# turntable.net
KiCad netlist of a schematic drawn in EAGLE
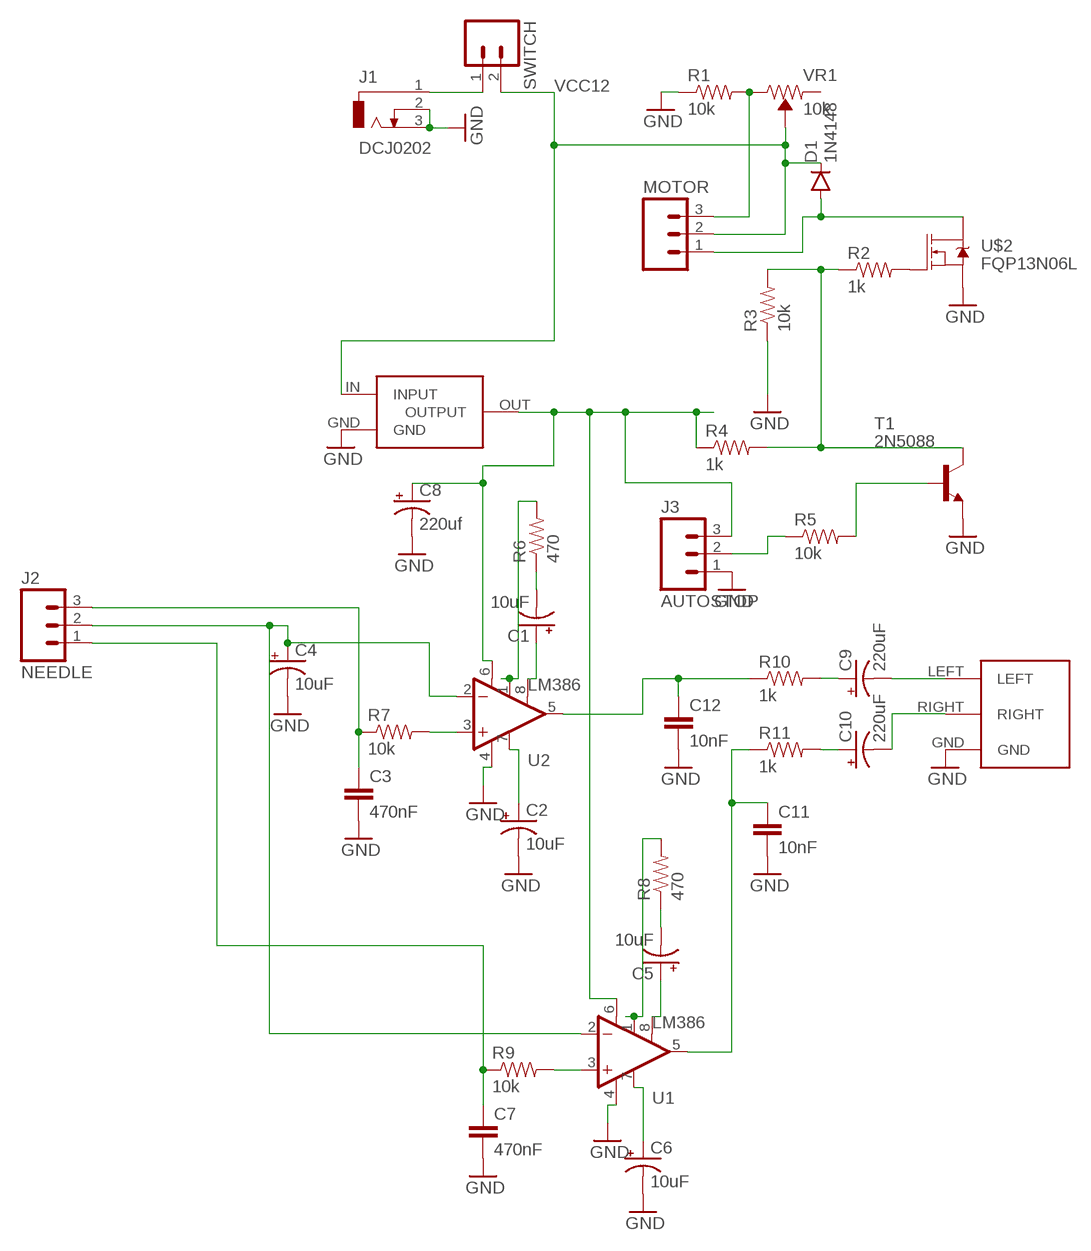
[diagram p0: schematic, sheet 1]

(export (version "E")
  (design (tool "Eeschema 10.0.6"))
  (components
    (comp (ref "C1")
      (value "10uF")
      (footprint "eagle-import:E5-5")
      (libsource (lib "eagle-import") (part "CPOL-USE5-5"))
    )
    (comp (ref "C2")
      (value "10uF")
      (footprint "eagle-import:E5-5")
      (libsource (lib "eagle-import") (part "CPOL-USE5-5"))
    )
    (comp (ref "C3")
      (value "470nF")
      (footprint "eagle-import:C15B8")
      (libsource (lib "eagle-import") (part "C15/8"))
    )
    (comp (ref "C4")
      (value "10uF")
      (footprint "eagle-import:E5-5")
      (libsource (lib "eagle-import") (part "CPOL-USE5-5"))
    )
    (comp (ref "C5")
      (value "10uF")
      (footprint "eagle-import:E5-5")
      (libsource (lib "eagle-import") (part "CPOL-USE5-5"))
    )
    (comp (ref "C6")
      (value "10uF")
      (footprint "eagle-import:E5-5")
      (libsource (lib "eagle-import") (part "CPOL-USE5-5"))
    )
    (comp (ref "C7")
      (value "470nF")
      (footprint "eagle-import:C15B8")
      (libsource (lib "eagle-import") (part "C15/8"))
    )
    (comp (ref "C8")
      (value "220uf")
      (footprint "eagle-import:TT5D10")
      (libsource (lib "eagle-import") (part "CPOL-USTT5D10"))
    )
    (comp (ref "C9")
      (value "220uF")
      (footprint "eagle-import:E5-5")
      (libsource (lib "eagle-import") (part "CPOL-USE5-5"))
    )
    (comp (ref "C10")
      (value "220uF")
      (footprint "eagle-import:E5-5")
      (libsource (lib "eagle-import") (part "CPOL-USE5-5"))
    )
    (comp (ref "C11")
      (value "10nF")
      (footprint "eagle-import:C5B2.5")
      (libsource (lib "eagle-import") (part "C5/2.5"))
    )
    (comp (ref "C12")
      (value "10nF")
      (footprint "eagle-import:C5B2.5")
      (libsource (lib "eagle-import") (part "C5/2.5"))
    )
    (comp (ref "D1")
      (value "1N4148")
      (footprint "eagle-import:DIODE-1N4148")
      (libsource (lib "eagle-import") (part "DIODE1N4148"))
    )
    (comp (ref "J1")
      (value "DCJ0202")
      (footprint "eagle-import:DCJ0202")
      (libsource (lib "eagle-import") (part "DCJ0202"))
    )
    (comp (ref "J2")
      (value "NEEDLE")
      (footprint "eagle-import:1X03")
      (libsource (lib "eagle-import") (part "M03PTH"))
    )
    (comp (ref "J3")
      (value "AUTOSTOP")
      (footprint "eagle-import:1X03")
      (libsource (lib "eagle-import") (part "M03PTH"))
    )
    (comp (ref "MOTOR")
      (value "M03PTH")
      (footprint "eagle-import:1X03")
      (libsource (lib "eagle-import") (part "M03PTH"))
    )
    (comp (ref "R1")
      (value "10k")
      (footprint "eagle-import:AXIAL-0.5")
      (libsource (lib "eagle-import") (part "RESISTORPTH-1/2W"))
    )
    (comp (ref "R2")
      (value "1k")
      (footprint "eagle-import:AXIAL-0.5")
      (libsource (lib "eagle-import") (part "RESISTORPTH-1/2W"))
    )
    (comp (ref "R3")
      (value "10k")
      (footprint "eagle-import:AXIAL-0.5")
      (libsource (lib "eagle-import") (part "RESISTORPTH-1/2W"))
    )
    (comp (ref "R4")
      (value "1k")
      (footprint "eagle-import:AXIAL-0.5")
      (libsource (lib "eagle-import") (part "RESISTORPTH-1/2W"))
    )
    (comp (ref "R5")
      (value "10k")
      (footprint "eagle-import:AXIAL-0.5")
      (libsource (lib "eagle-import") (part "RESISTORPTH-1/2W"))
    )
    (comp (ref "R6")
      (value "470")
      (footprint "eagle-import:AXIAL-0.5")
      (libsource (lib "eagle-import") (part "RESISTORPTH-1/2W"))
    )
    (comp (ref "R7")
      (value "10k")
      (footprint "eagle-import:AXIAL-0.5")
      (libsource (lib "eagle-import") (part "RESISTORPTH-1/2W"))
    )
    (comp (ref "R8")
      (value "470")
      (footprint "eagle-import:AXIAL-0.5")
      (libsource (lib "eagle-import") (part "RESISTORPTH-1/2W"))
    )
    (comp (ref "R9")
      (value "10k")
      (footprint "eagle-import:AXIAL-0.5")
      (libsource (lib "eagle-import") (part "RESISTORPTH-1/2W"))
    )
    (comp (ref "R10")
      (value "1k")
      (footprint "eagle-import:AXIAL-0.5")
      (libsource (lib "eagle-import") (part "RESISTORPTH-1/2W"))
    )
    (comp (ref "R11")
      (value "1k")
      (footprint "eagle-import:AXIAL-0.5")
      (libsource (lib "eagle-import") (part "RESISTORPTH-1/2W"))
    )
    (comp (ref "SWITCH")
      (value "M02PTH")
      (footprint "eagle-import:1X02")
      (libsource (lib "eagle-import") (part "M02PTH"))
    )
    (comp (ref "T1")
      (value "2N5088")
      (footprint "eagle-import:TO92")
      (libsource (lib "eagle-import") (part "2N5088"))
    )
    (comp (ref "U$1")
      (value "LD1117")
      (footprint "eagle-import:78XXL")
      (libsource (lib "eagle-import") (part "LD1117"))
    )
    (comp (ref "U$2")
      (value "FQP13N06L")
      (footprint "eagle-import:TO-220")
      (libsource (lib "eagle-import") (part "FQP13N06L"))
    )
    (comp (ref "U$3")
      (value "RCA")
      (footprint "eagle-import:RCA")
      (libsource (lib "eagle-import") (part "RCA"))
    )
    (comp (ref "U1")
      (value "LM386")
      (footprint "eagle-import:DIP08")
      (libsource (lib "eagle-import") (part "LM386"))
    )
    (comp (ref "U2")
      (value "LM386")
      (footprint "eagle-import:DIP08")
      (libsource (lib "eagle-import") (part "LM386"))
    )
    (comp (ref "VR1")
      (value "10k")
      (footprint "eagle-import:TRIMPOT-PTH-3386U")
      (libsource (lib "eagle-import") (part "TRIMPOT-PTH-10MM-KNOB-1/2W-10%"))
    )
  )
  (nets
    (net (code "1") (name "/VCC12") (class "Default")
      (node (ref "D1") (pin "C") (pinfunction "C_C") (pintype "passive"))
      (node (ref "MOTOR") (pin "2") (pinfunction "2_2") (pintype "passive"))
      (node (ref "SWITCH") (pin "2") (pinfunction "2_2") (pintype "passive"))
      (node (ref "U$1") (pin "IN") (pinfunction "INPUT_IN") (pintype "bidirectional"))
      (node (ref "VR1") (pin "2") (pinfunction "WIPER_2") (pintype "passive"))
    )
    (net (code "2") (name "GND") (class "Default")
      (node (ref "C11") (pin "2") (pinfunction "2_2") (pintype "passive"))
      (node (ref "C12") (pin "2") (pinfunction "2_2") (pintype "passive"))
      (node (ref "C2") (pin "-") (pinfunction "-_-") (pintype "passive"))
      (node (ref "C3") (pin "2") (pinfunction "2_2") (pintype "passive"))
      (node (ref "C4") (pin "-") (pinfunction "-_-") (pintype "passive"))
      (node (ref "C6") (pin "-") (pinfunction "-_-") (pintype "passive"))
      (node (ref "C7") (pin "2") (pinfunction "2_2") (pintype "passive"))
      (node (ref "C8") (pin "-") (pinfunction "-_-") (pintype "passive"))
      (node (ref "J1") (pin "2") (pinfunction "2_2") (pintype "passive"))
      (node (ref "J1") (pin "3") (pinfunction "3_3") (pintype "passive"))
      (node (ref "J3") (pin "1") (pinfunction "1_1") (pintype "passive"))
      (node (ref "R1") (pin "P$1") (pinfunction "1_P$1") (pintype "passive"))
      (node (ref "R3") (pin "P$1") (pinfunction "1_P$1") (pintype "passive"))
      (node (ref "T1") (pin "3") (pinfunction "E_3") (pintype "passive"))
      (node (ref "U$1") (pin "GND") (pinfunction "GND_GND") (pintype "bidirectional"))
      (node (ref "U$2") (pin "S") (pinfunction "S_S") (pintype "bidirectional"))
      (node (ref "U$3") (pin "GND") (pinfunction "GND_GND") (pintype "bidirectional"))
      (node (ref "U1") (pin "4") (pinfunction "V-_4") (pintype "power_in"))
      (node (ref "U2") (pin "4") (pinfunction "V-_4") (pintype "power_in"))
    )
    (net (code "3") (name "Net-(C1-Pad+)") (class "Default")
      (node (ref "C1") (pin "+") (pinfunction "+_+") (pintype "passive"))
      (node (ref "U2") (pin "8") (pinfunction "GAIN_8") (pintype "bidirectional"))
    )
    (net (code "4") (name "Net-(C5-Pad+)") (class "Default")
      (node (ref "C5") (pin "+") (pinfunction "+_+") (pintype "passive"))
      (node (ref "U1") (pin "8") (pinfunction "GAIN_8") (pintype "bidirectional"))
    )
    (net (code "5") (name "Net-(C9-Pad-)") (class "Default")
      (node (ref "C9") (pin "-") (pinfunction "-_-") (pintype "passive"))
      (node (ref "U$3") (pin "LEFT") (pinfunction "LEFT_LEFT") (pintype "bidirectional"))
    )
    (net (code "6") (name "Net-(C10-Pad-)") (class "Default")
      (node (ref "C10") (pin "-") (pinfunction "-_-") (pintype "passive"))
      (node (ref "U$3") (pin "RIGHT") (pinfunction "RIGHT_RIGHT") (pintype "bidirectional"))
    )
    (net (code "7") (name "Net-(D1-PadA)") (class "Default")
      (node (ref "D1") (pin "A") (pinfunction "A_A") (pintype "passive"))
      (node (ref "MOTOR") (pin "1") (pinfunction "1_1") (pintype "passive"))
      (node (ref "U$2") (pin "D") (pinfunction "D_D") (pintype "bidirectional"))
    )
    (net (code "8") (name "Net-(J1-Pad1)") (class "Default")
      (node (ref "J1") (pin "1") (pinfunction "1_1") (pintype "passive"))
      (node (ref "SWITCH") (pin "1") (pinfunction "1_1") (pintype "passive"))
    )
    (net (code "9") (name "Net-(R1-2)") (class "Default")
      (node (ref "MOTOR") (pin "3") (pinfunction "3_3") (pintype "passive"))
      (node (ref "R1") (pin "P$2") (pinfunction "2_P$2") (pintype "passive"))
      (node (ref "VR1") (pin "3") (pinfunction "CW_3") (pintype "passive"))
    )
    (net (code "10") (name "Net-(R2-1)") (class "Default")
      (node (ref "R2") (pin "P$1") (pinfunction "1_P$1") (pintype "passive"))
      (node (ref "R3") (pin "P$2") (pinfunction "2_P$2") (pintype "passive"))
      (node (ref "R4") (pin "P$2") (pinfunction "2_P$2") (pintype "passive"))
      (node (ref "T1") (pin "1") (pinfunction "C_1") (pintype "passive"))
    )
    (net (code "11") (name "Net-(R2-2)") (class "Default")
      (node (ref "R2") (pin "P$2") (pinfunction "2_P$2") (pintype "passive"))
      (node (ref "U$2") (pin "G") (pinfunction "G_G") (pintype "bidirectional"))
    )
    (net (code "12") (name "Net-(R4-1)") (class "Default")
      (node (ref "C8") (pin "+") (pinfunction "+_+") (pintype "passive"))
      (node (ref "J3") (pin "3") (pinfunction "3_3") (pintype "passive"))
      (node (ref "R4") (pin "P$1") (pinfunction "1_P$1") (pintype "passive"))
      (node (ref "U$1") (pin "OUT") (pinfunction "OUTPUT_OUT") (pintype "bidirectional"))
      (node (ref "U1") (pin "6") (pinfunction "V+_6") (pintype "power_in"))
      (node (ref "U2") (pin "6") (pinfunction "V+_6") (pintype "power_in"))
    )
    (net (code "13") (name "Net-(R5-1)") (class "Default")
      (node (ref "J3") (pin "2") (pinfunction "2_2") (pintype "passive"))
      (node (ref "R5") (pin "P$1") (pinfunction "1_P$1") (pintype "passive"))
    )
    (net (code "14") (name "Net-(R5-2)") (class "Default")
      (node (ref "R5") (pin "P$2") (pinfunction "2_P$2") (pintype "passive"))
      (node (ref "T1") (pin "2") (pinfunction "B_2") (pintype "passive"))
    )
    (net (code "15") (name "Net-(R6-1)") (class "Default")
      (node (ref "C1") (pin "-") (pinfunction "-_-") (pintype "passive"))
      (node (ref "R6") (pin "P$1") (pinfunction "1_P$1") (pintype "passive"))
    )
    (net (code "16") (name "Net-(R6-2)") (class "Default")
      (node (ref "R6") (pin "P$2") (pinfunction "2_P$2") (pintype "passive"))
      (node (ref "U2") (pin "1") (pinfunction "GAIN_1") (pintype "bidirectional"))
    )
    (net (code "17") (name "Net-(R7-1)") (class "Default")
      (node (ref "C3") (pin "1") (pinfunction "1_1") (pintype "passive"))
      (node (ref "J2") (pin "3") (pinfunction "3_3") (pintype "passive"))
      (node (ref "R7") (pin "P$1") (pinfunction "1_P$1") (pintype "passive"))
    )
    (net (code "18") (name "Net-(R7-2)") (class "Default")
      (node (ref "R7") (pin "P$2") (pinfunction "2_P$2") (pintype "passive"))
      (node (ref "U2") (pin "3") (pinfunction "+IN_3") (pintype "input"))
    )
    (net (code "19") (name "Net-(R8-1)") (class "Default")
      (node (ref "C5") (pin "-") (pinfunction "-_-") (pintype "passive"))
      (node (ref "R8") (pin "P$1") (pinfunction "1_P$1") (pintype "passive"))
    )
    (net (code "20") (name "Net-(R8-2)") (class "Default")
      (node (ref "R8") (pin "P$2") (pinfunction "2_P$2") (pintype "passive"))
      (node (ref "U1") (pin "1") (pinfunction "GAIN_1") (pintype "bidirectional"))
    )
    (net (code "21") (name "Net-(R9-1)") (class "Default")
      (node (ref "C7") (pin "1") (pinfunction "1_1") (pintype "passive"))
      (node (ref "J2") (pin "1") (pinfunction "1_1") (pintype "passive"))
      (node (ref "R9") (pin "P$1") (pinfunction "1_P$1") (pintype "passive"))
    )
    (net (code "22") (name "Net-(R9-2)") (class "Default")
      (node (ref "R9") (pin "P$2") (pinfunction "2_P$2") (pintype "passive"))
      (node (ref "U1") (pin "3") (pinfunction "+IN_3") (pintype "input"))
    )
    (net (code "23") (name "Net-(R10-1)") (class "Default")
      (node (ref "C12") (pin "1") (pinfunction "1_1") (pintype "passive"))
      (node (ref "R10") (pin "P$1") (pinfunction "1_P$1") (pintype "passive"))
      (node (ref "U2") (pin "5") (pinfunction "OUT_5") (pintype "output"))
    )
    (net (code "24") (name "Net-(R10-2)") (class "Default")
      (node (ref "C9") (pin "+") (pinfunction "+_+") (pintype "passive"))
      (node (ref "R10") (pin "P$2") (pinfunction "2_P$2") (pintype "passive"))
    )
    (net (code "25") (name "Net-(R11-1)") (class "Default")
      (node (ref "C11") (pin "1") (pinfunction "1_1") (pintype "passive"))
      (node (ref "R11") (pin "P$1") (pinfunction "1_P$1") (pintype "passive"))
      (node (ref "U1") (pin "5") (pinfunction "OUT_5") (pintype "output"))
    )
    (net (code "26") (name "Net-(R11-2)") (class "Default")
      (node (ref "C10") (pin "+") (pinfunction "+_+") (pintype "passive"))
      (node (ref "R11") (pin "P$2") (pinfunction "2_P$2") (pintype "passive"))
    )
    (net (code "27") (name "Net-(U1--IN)") (class "Default")
      (node (ref "C4") (pin "+") (pinfunction "+_+") (pintype "passive"))
      (node (ref "J2") (pin "2") (pinfunction "2_2") (pintype "passive"))
      (node (ref "U1") (pin "2") (pinfunction "-IN_2") (pintype "input"))
      (node (ref "U2") (pin "2") (pinfunction "-IN_2") (pintype "input"))
    )
    (net (code "28") (name "Net-(U1-BP)") (class "Default")
      (node (ref "C6") (pin "+") (pinfunction "+_+") (pintype "passive"))
      (node (ref "U1") (pin "7") (pinfunction "BP_7") (pintype "bidirectional"))
    )
    (net (code "29") (name "Net-(U2-BP)") (class "Default")
      (node (ref "C2") (pin "+") (pinfunction "+_+") (pintype "passive"))
      (node (ref "U2") (pin "7") (pinfunction "BP_7") (pintype "bidirectional"))
    )
    (net (code "30") (name "unconnected-(VR1-CCW-Pad1)") (class "Default")
      (node (ref "VR1") (pin "1") (pinfunction "CCW_1") (pintype "passive"))
    )
  )
)
